# Monoblink.net
KiCad netlist of a schematic drawn in EAGLE
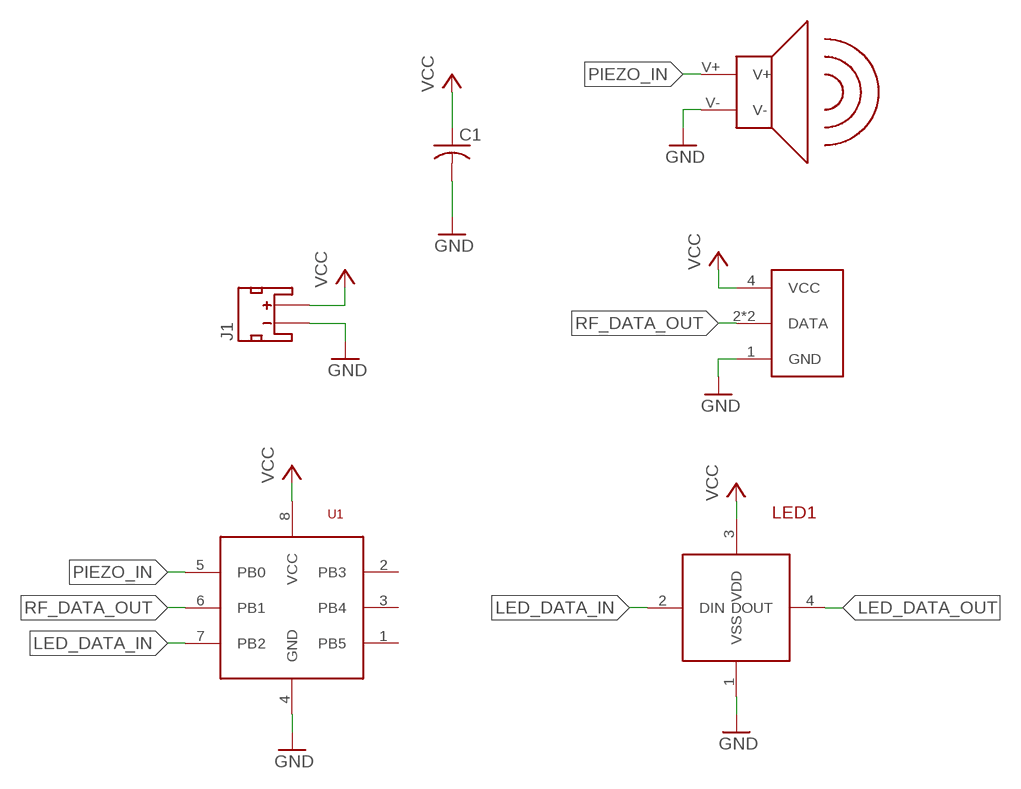
[diagram p0: schematic, sheet 1]

(export (version "E")
  (design (tool "Eeschema 10.0.6"))
  (components
    (comp (ref "C1")
      (value "C-USC0805")
      (footprint "eagle-import:C0805")
      (libsource (lib "eagle-import") (part "C-USC0805"))
    )
    (comp (ref "J1")
      (value "BATT_CONN")
      (footprint "eagle-import:JST-2-SMD")
      (libsource (lib "eagle-import") (part "BATT_CONN"))
    )
    (comp (ref "LED1")
      (value "NEOPIXEL")
      (footprint "eagle-import:SMD5050")
      (libsource (lib "eagle-import") (part "NEOPIXEL"))
    )
    (comp (ref "U$1")
      (value "RF_CONN")
      (footprint "eagle-import:RF_CONN")
      (libsource (lib "eagle-import") (part "RF_CONN"))
    )
    (comp (ref "U$2")
      (value "PIEZO")
      (footprint "eagle-import:PS1240P02BT")
      (libsource (lib "eagle-import") (part "PIEZO"))
    )
    (comp (ref "U1")
      (value "ATTINY85")
      (footprint "eagle-import:SOIC8")
      (libsource (lib "eagle-import") (part "ATTINY85"))
    )
  )
  (nets
    (net (code "1") (name "GND") (class "Default")
      (node (ref "C1") (pin "2") (pinfunction "2_2") (pintype "passive"))
      (node (ref "J1") (pin "1") (pinfunction "-_1") (pintype "bidirectional"))
      (node (ref "LED1") (pin "1") (pinfunction "VSS_1") (pintype "bidirectional"))
      (node (ref "U$1") (pin "1") (pinfunction "GND_1") (pintype "bidirectional"))
      (node (ref "U$2") (pin "V-") (pinfunction "V-_V-") (pintype "bidirectional"))
      (node (ref "U1") (pin "4") (pinfunction "GND_4") (pintype "bidirectional"))
    )
    (net (code "2") (name "LED_DATA_IN") (class "Default")
      (node (ref "LED1") (pin "2") (pinfunction "DIN_2") (pintype "bidirectional"))
      (node (ref "U1") (pin "7") (pinfunction "PB2_7") (pintype "bidirectional"))
    )
    (net (code "3") (name "LED_DATA_OUT") (class "Default")
      (node (ref "LED1") (pin "4") (pinfunction "DOUT_4") (pintype "bidirectional"))
    )
    (net (code "4") (name "PIEZO_IN") (class "Default")
      (node (ref "U$2") (pin "V+") (pinfunction "V+_V+") (pintype "bidirectional"))
      (node (ref "U1") (pin "5") (pinfunction "PB0_5") (pintype "bidirectional"))
    )
    (net (code "5") (name "RF_DATA_OUT") (class "Default")
      (node (ref "U$1") (pin "2") (pinfunction "DATA_2") (pintype "bidirectional"))
      (node (ref "U$1") (pin "3") (pinfunction "DATA_3") (pintype "bidirectional"))
      (node (ref "U1") (pin "6") (pinfunction "PB1_6") (pintype "bidirectional"))
    )
    (net (code "6") (name "VCC") (class "Default")
      (node (ref "C1") (pin "1") (pinfunction "1_1") (pintype "passive"))
      (node (ref "J1") (pin "2") (pinfunction "+_2") (pintype "bidirectional"))
      (node (ref "LED1") (pin "3") (pinfunction "VDD_3") (pintype "bidirectional"))
      (node (ref "U$1") (pin "4") (pinfunction "VCC_4") (pintype "bidirectional"))
      (node (ref "U1") (pin "8") (pinfunction "VCC_8") (pintype "bidirectional"))
    )
    (net (code "7") (name "unconnected-(J1-PAD1-PadNC1)") (class "Default")
      (node (ref "J1") (pin "NC1") (pinfunction "PAD1_NC1") (pintype "bidirectional"))
    )
    (net (code "8") (name "unconnected-(J1-PAD2-PadNC2)") (class "Default")
      (node (ref "J1") (pin "NC2") (pinfunction "PAD2_NC2") (pintype "bidirectional"))
    )
    (net (code "9") (name "unconnected-(U1-PB3-Pad2)") (class "Default")
      (node (ref "U1") (pin "2") (pinfunction "PB3_2") (pintype "bidirectional"))
    )
    (net (code "10") (name "unconnected-(U1-PB4-Pad3)") (class "Default")
      (node (ref "U1") (pin "3") (pinfunction "PB4_3") (pintype "bidirectional"))
    )
    (net (code "11") (name "unconnected-(U1-PB5-Pad1)") (class "Default")
      (node (ref "U1") (pin "1") (pinfunction "PB5_1") (pintype "bidirectional"))
    )
  )
)
